# rpi4pcie.net
KiCad netlist of a schematic drawn in EAGLE
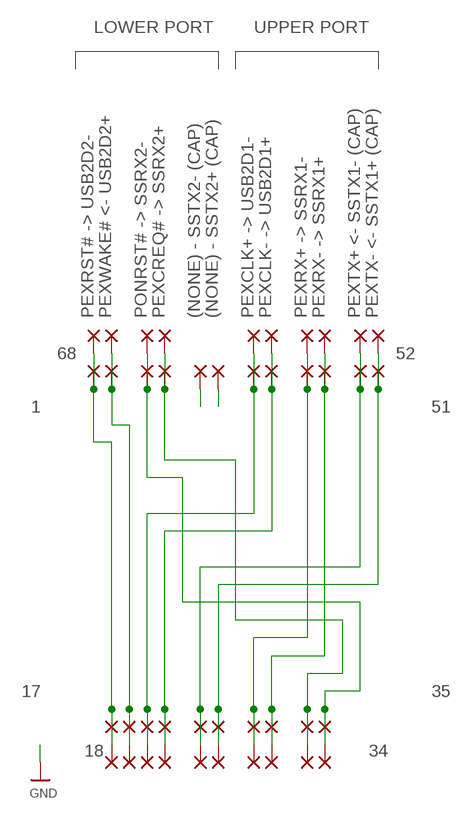
[diagram p0: schematic, sheet 1]

(export (version "E")
  (design (tool "Eeschema 10.0.6"))
  (components
    (comp (ref "PAD19")
      (value "PADQFN-0.4")
      (footprint "eagle-import:PAD-QFN-0.4")
      (libsource (lib "eagle-import") (part "PADQFN-0.4"))
    )
    (comp (ref "PAD20")
      (value "PADQFN-0.4")
      (footprint "eagle-import:PAD-QFN-0.4")
      (libsource (lib "eagle-import") (part "PADQFN-0.4"))
    )
    (comp (ref "PAD21")
      (value "PADQFN-0.4")
      (footprint "eagle-import:PAD-QFN-0.4")
      (libsource (lib "eagle-import") (part "PADQFN-0.4"))
    )
    (comp (ref "PAD22")
      (value "PADQFN-0.4")
      (footprint "eagle-import:PAD-QFN-0.4")
      (libsource (lib "eagle-import") (part "PADQFN-0.4"))
    )
    (comp (ref "PAD24")
      (value "PADQFN-0.4")
      (footprint "eagle-import:PAD-QFN-0.4")
      (libsource (lib "eagle-import") (part "PADQFN-0.4"))
    )
    (comp (ref "PAD25")
      (value "PADQFN-0.4")
      (footprint "eagle-import:PAD-QFN-0.4")
      (libsource (lib "eagle-import") (part "PADQFN-0.4"))
    )
    (comp (ref "PAD27")
      (value "PADQFN-0.4")
      (footprint "eagle-import:PAD-QFN-0.4")
      (libsource (lib "eagle-import") (part "PADQFN-0.4"))
    )
    (comp (ref "PAD28")
      (value "PADQFN-0.4")
      (footprint "eagle-import:PAD-QFN-0.4")
      (libsource (lib "eagle-import") (part "PADQFN-0.4"))
    )
    (comp (ref "PAD30")
      (value "PADQFN-0.4")
      (footprint "eagle-import:PAD-QFN-0.4")
      (libsource (lib "eagle-import") (part "PADQFN-0.4"))
    )
    (comp (ref "PAD31")
      (value "PADQFN-0.4")
      (footprint "eagle-import:PAD-QFN-0.4")
      (libsource (lib "eagle-import") (part "PADQFN-0.4"))
    )
    (comp (ref "PAD52")
      (value "PADQFN-0.4")
      (footprint "eagle-import:PAD-QFN-0.4")
      (libsource (lib "eagle-import") (part "PADQFN-0.4"))
    )
    (comp (ref "PAD53")
      (value "PADQFN-0.4")
      (footprint "eagle-import:PAD-QFN-0.4")
      (libsource (lib "eagle-import") (part "PADQFN-0.4"))
    )
    (comp (ref "PAD55")
      (value "PADQFN-0.4")
      (footprint "eagle-import:PAD-QFN-0.4")
      (libsource (lib "eagle-import") (part "PADQFN-0.4"))
    )
    (comp (ref "PAD56")
      (value "PADQFN-0.4")
      (footprint "eagle-import:PAD-QFN-0.4")
      (libsource (lib "eagle-import") (part "PADQFN-0.4"))
    )
    (comp (ref "PAD58")
      (value "PADQFN-0.4")
      (footprint "eagle-import:PAD-QFN-0.4")
      (libsource (lib "eagle-import") (part "PADQFN-0.4"))
    )
    (comp (ref "PAD59")
      (value "PADQFN-0.4")
      (footprint "eagle-import:PAD-QFN-0.4")
      (libsource (lib "eagle-import") (part "PADQFN-0.4"))
    )
    (comp (ref "PAD61")
      (value "PADQFN-0.4")
      (footprint "eagle-import:PAD-QFN-0.4")
      (libsource (lib "eagle-import") (part "PADQFN-0.4"))
    )
    (comp (ref "PAD62")
      (value "PADQFN-0.4")
      (footprint "eagle-import:PAD-QFN-0.4")
      (libsource (lib "eagle-import") (part "PADQFN-0.4"))
    )
    (comp (ref "PAD64")
      (value "PADQFN-0.4")
      (footprint "eagle-import:PAD-QFN-0.4")
      (libsource (lib "eagle-import") (part "PADQFN-0.4"))
    )
    (comp (ref "PAD65")
      (value "PADQFN-0.4")
      (footprint "eagle-import:PAD-QFN-0.4")
      (libsource (lib "eagle-import") (part "PADQFN-0.4"))
    )
    (comp (ref "PAD67")
      (value "PADQFN-0.4")
      (footprint "eagle-import:PAD-QFN-0.4")
      (libsource (lib "eagle-import") (part "PADQFN-0.4"))
    )
    (comp (ref "PAD68")
      (value "PADQFN-0.4")
      (footprint "eagle-import:PAD-QFN-0.4")
      (libsource (lib "eagle-import") (part "PADQFN-0.4"))
    )
    (comp (ref "PAD69")
      (value "PADQFN-0.4")
      (footprint "eagle-import:PAD-QFN-0.4")
      (libsource (lib "eagle-import") (part "PADQFN-0.4"))
    )
    (comp (ref "PAD70")
      (value "PADQFN-0.4")
      (footprint "eagle-import:PAD-QFN-0.4")
      (libsource (lib "eagle-import") (part "PADQFN-0.4"))
    )
    (comp (ref "PAD71")
      (value "PADQFN-0.4")
      (footprint "eagle-import:PAD-QFN-0.4")
      (libsource (lib "eagle-import") (part "PADQFN-0.4"))
    )
    (comp (ref "PAD72")
      (value "PADQFN-0.4")
      (footprint "eagle-import:PAD-QFN-0.4")
      (libsource (lib "eagle-import") (part "PADQFN-0.4"))
    )
    (comp (ref "PAD73")
      (value "PADQFN-0.4")
      (footprint "eagle-import:PAD-QFN-0.4")
      (libsource (lib "eagle-import") (part "PADQFN-0.4"))
    )
    (comp (ref "PAD74")
      (value "PADQFN-0.4")
      (footprint "eagle-import:PAD-QFN-0.4")
      (libsource (lib "eagle-import") (part "PADQFN-0.4"))
    )
    (comp (ref "PAD75")
      (value "PADQFN-0.4")
      (footprint "eagle-import:PAD-QFN-0.4")
      (libsource (lib "eagle-import") (part "PADQFN-0.4"))
    )
    (comp (ref "PAD76")
      (value "PADQFN-0.4")
      (footprint "eagle-import:PAD-QFN-0.4")
      (libsource (lib "eagle-import") (part "PADQFN-0.4"))
    )
    (comp (ref "PAD77")
      (value "PADQFN-0.4")
      (footprint "eagle-import:PAD-QFN-0.4")
      (libsource (lib "eagle-import") (part "PADQFN-0.4"))
    )
    (comp (ref "PAD78")
      (value "PADQFN-0.4")
      (footprint "eagle-import:PAD-QFN-0.4")
      (libsource (lib "eagle-import") (part "PADQFN-0.4"))
    )
    (comp (ref "PAD79")
      (value "PADQFN-0.4")
      (footprint "eagle-import:PAD-QFN-0.4")
      (libsource (lib "eagle-import") (part "PADQFN-0.4"))
    )
    (comp (ref "PAD80")
      (value "PADQFN-0.4")
      (footprint "eagle-import:PAD-QFN-0.4")
      (libsource (lib "eagle-import") (part "PADQFN-0.4"))
    )
    (comp (ref "PAD81")
      (value "PADQFN-0.4")
      (footprint "eagle-import:PAD-QFN-0.4")
      (libsource (lib "eagle-import") (part "PADQFN-0.4"))
    )
    (comp (ref "PAD82")
      (value "PADQFN-0.4")
      (footprint "eagle-import:PAD-QFN-0.4")
      (libsource (lib "eagle-import") (part "PADQFN-0.4"))
    )
    (comp (ref "PAD83")
      (value "PADQFN-0.4")
      (footprint "eagle-import:PAD-QFN-0.4")
      (libsource (lib "eagle-import") (part "PADQFN-0.4"))
    )
    (comp (ref "PAD84")
      (value "PADQFN-0.4")
      (footprint "eagle-import:PAD-QFN-0.4")
      (libsource (lib "eagle-import") (part "PADQFN-0.4"))
    )
    (comp (ref "PAD85")
      (value "PADQFN-0.4")
      (footprint "eagle-import:PAD-QFN-0.4")
      (libsource (lib "eagle-import") (part "PADQFN-0.4"))
    )
    (comp (ref "PAD86")
      (value "PADQFN-0.4")
      (footprint "eagle-import:PAD-QFN-0.4")
      (libsource (lib "eagle-import") (part "PADQFN-0.4"))
    )
    (comp (ref "PAD87")
      (value "PADQFN-0.4")
      (footprint "eagle-import:PAD-QFN-0.4")
      (libsource (lib "eagle-import") (part "PADQFN-0.4"))
    )
    (comp (ref "PAD88")
      (value "PADQFN-0.4")
      (footprint "eagle-import:PAD-QFN-0.4")
      (libsource (lib "eagle-import") (part "PADQFN-0.4"))
    )
  )
  (nets
    (net (code "2") (name "Net-(PAD19-P$1)") (class "Default")
      (node (ref "PAD19") (pin "1") (pinfunction "P$1_1") (pintype "passive"))
      (node (ref "PAD68") (pin "1") (pinfunction "P$1_1") (pintype "passive"))
      (node (ref "PAD69") (pin "1") (pinfunction "P$1_1") (pintype "passive"))
      (node (ref "PAD77") (pin "1") (pinfunction "P$1_1") (pintype "passive"))
    )
    (net (code "3") (name "Net-(PAD20-P$1)") (class "Default")
      (node (ref "PAD20") (pin "1") (pinfunction "P$1_1") (pintype "passive"))
      (node (ref "PAD67") (pin "1") (pinfunction "P$1_1") (pintype "passive"))
      (node (ref "PAD70") (pin "1") (pinfunction "P$1_1") (pintype "passive"))
      (node (ref "PAD78") (pin "1") (pinfunction "P$1_1") (pintype "passive"))
    )
    (net (code "4") (name "Net-(PAD21-P$1)") (class "Default")
      (node (ref "PAD21") (pin "1") (pinfunction "P$1_1") (pintype "passive"))
      (node (ref "PAD59") (pin "1") (pinfunction "P$1_1") (pintype "passive"))
      (node (ref "PAD71") (pin "1") (pinfunction "P$1_1") (pintype "passive"))
      (node (ref "PAD79") (pin "1") (pinfunction "P$1_1") (pintype "passive"))
    )
    (net (code "5") (name "Net-(PAD22-P$1)") (class "Default")
      (node (ref "PAD22") (pin "1") (pinfunction "P$1_1") (pintype "passive"))
      (node (ref "PAD58") (pin "1") (pinfunction "P$1_1") (pintype "passive"))
      (node (ref "PAD72") (pin "1") (pinfunction "P$1_1") (pintype "passive"))
      (node (ref "PAD80") (pin "1") (pinfunction "P$1_1") (pintype "passive"))
    )
    (net (code "6") (name "Net-(PAD24-P$1)") (class "Default")
      (node (ref "PAD24") (pin "1") (pinfunction "P$1_1") (pintype "passive"))
      (node (ref "PAD53") (pin "1") (pinfunction "P$1_1") (pintype "passive"))
      (node (ref "PAD75") (pin "1") (pinfunction "P$1_1") (pintype "passive"))
      (node (ref "PAD81") (pin "1") (pinfunction "P$1_1") (pintype "passive"))
    )
    (net (code "7") (name "Net-(PAD25-P$1)") (class "Default")
      (node (ref "PAD25") (pin "1") (pinfunction "P$1_1") (pintype "passive"))
      (node (ref "PAD52") (pin "1") (pinfunction "P$1_1") (pintype "passive"))
      (node (ref "PAD76") (pin "1") (pinfunction "P$1_1") (pintype "passive"))
      (node (ref "PAD82") (pin "1") (pinfunction "P$1_1") (pintype "passive"))
    )
    (net (code "8") (name "Net-(PAD27-P$1)") (class "Default")
      (node (ref "PAD27") (pin "1") (pinfunction "P$1_1") (pintype "passive"))
      (node (ref "PAD56") (pin "1") (pinfunction "P$1_1") (pintype "passive"))
      (node (ref "PAD73") (pin "1") (pinfunction "P$1_1") (pintype "passive"))
      (node (ref "PAD83") (pin "1") (pinfunction "P$1_1") (pintype "passive"))
    )
    (net (code "9") (name "Net-(PAD28-P$1)") (class "Default")
      (node (ref "PAD28") (pin "1") (pinfunction "P$1_1") (pintype "passive"))
      (node (ref "PAD55") (pin "1") (pinfunction "P$1_1") (pintype "passive"))
      (node (ref "PAD74") (pin "1") (pinfunction "P$1_1") (pintype "passive"))
      (node (ref "PAD84") (pin "1") (pinfunction "P$1_1") (pintype "passive"))
    )
    (net (code "10") (name "Net-(PAD30-P$1)") (class "Default")
      (node (ref "PAD30") (pin "1") (pinfunction "P$1_1") (pintype "passive"))
      (node (ref "PAD64") (pin "1") (pinfunction "P$1_1") (pintype "passive"))
      (node (ref "PAD85") (pin "1") (pinfunction "P$1_1") (pintype "passive"))
      (node (ref "PAD88") (pin "1") (pinfunction "P$1_1") (pintype "passive"))
    )
    (net (code "11") (name "Net-(PAD31-P$1)") (class "Default")
      (node (ref "PAD31") (pin "1") (pinfunction "P$1_1") (pintype "passive"))
      (node (ref "PAD65") (pin "1") (pinfunction "P$1_1") (pintype "passive"))
      (node (ref "PAD86") (pin "1") (pinfunction "P$1_1") (pintype "passive"))
      (node (ref "PAD87") (pin "1") (pinfunction "P$1_1") (pintype "passive"))
    )
    (net (code "12") (name "unconnected-(PAD61-P$1-Pad1)") (class "Default")
      (node (ref "PAD61") (pin "1") (pinfunction "P$1_1") (pintype "passive"))
    )
    (net (code "13") (name "unconnected-(PAD62-P$1-Pad1)") (class "Default")
      (node (ref "PAD62") (pin "1") (pinfunction "P$1_1") (pintype "passive"))
    )
  )
)
